# CCR4.net
KiCad netlist of a schematic drawn in EAGLE
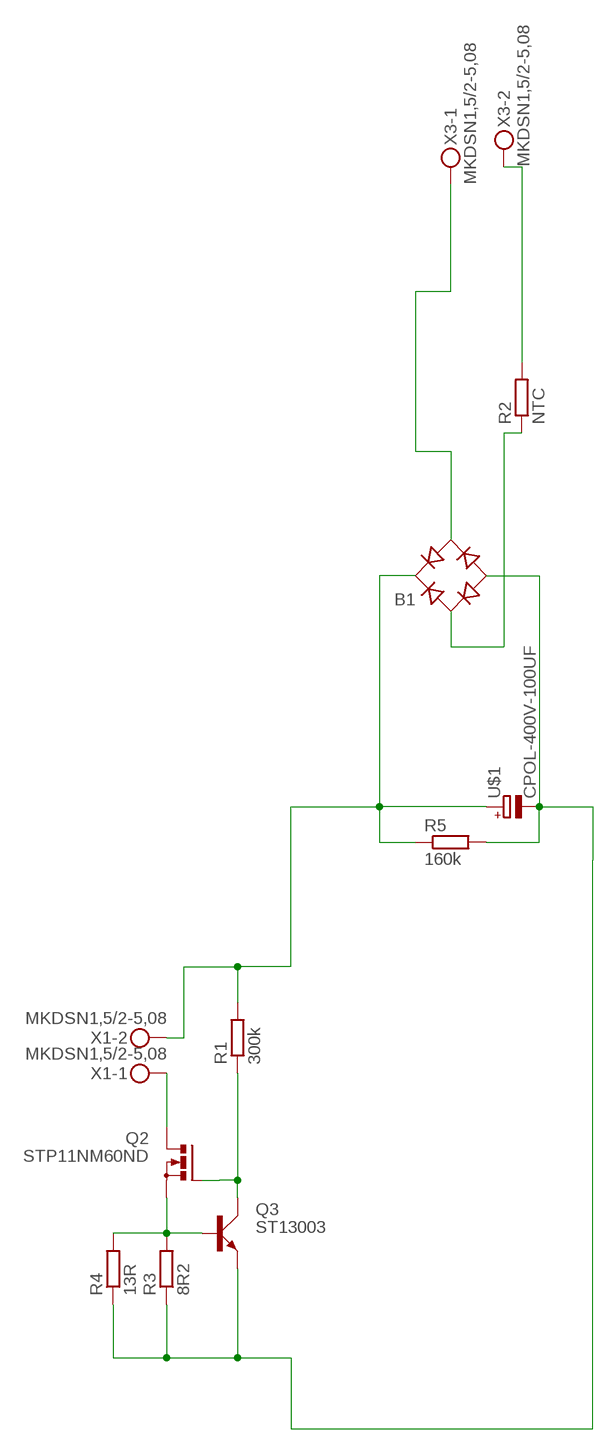
[diagram p0: schematic, sheet 1]

(export (version "E")
  (design (tool "Eeschema 10.0.6"))
  (components
    (comp (ref "B1")
      (value "RB1A")
      (footprint "eagle-import:RB1A")
      (libsource (lib "eagle-import") (part "RB1A"))
    )
    (comp (ref "Q2")
      (value "STP11NM60ND")
      (footprint "eagle-import:TO220BV")
      (libsource (lib "eagle-import") (part "BUZ11BV"))
    )
    (comp (ref "Q3")
      (value "ST13003")
      (footprint "eagle-import:SOT-92WIDE")
      (libsource (lib "eagle-import") (part "KSP42TA"))
    )
    (comp (ref "R1")
      (value "300k")
      (footprint "eagle-import:0411_12")
      (libsource (lib "eagle-import") (part "R-EU_0411/12"))
    )
    (comp (ref "R2")
      (value "NTC")
      (footprint "eagle-import:0309_10")
      (libsource (lib "eagle-import") (part "R-EU_0309/10"))
    )
    (comp (ref "R3")
      (value "8R2")
      (footprint "eagle-import:0411_12")
      (libsource (lib "eagle-import") (part "R-EU_0411/12"))
    )
    (comp (ref "R4")
      (value "13R")
      (footprint "eagle-import:0411_12")
      (libsource (lib "eagle-import") (part "R-EU_0411/12"))
    )
    (comp (ref "R5")
      (value "160k")
      (footprint "eagle-import:0204_7")
      (libsource (lib "eagle-import") (part "R-EU_0204/7"))
    )
    (comp (ref "U$1")
      (value "CPOL-400V-100UF")
      (footprint "eagle-import:18_36.5_7.62")
      (libsource (lib "eagle-import") (part "CPOL-400V-100UF"))
    )
    (comp (ref "X1")
      (value "MKDSN1,5/2-5,08")
      (footprint "eagle-import:MKDSN1,5_2-5,08")
      (libsource (lib "eagle-import") (part "MKDSN1,5/2-5,08"))
    )
    (comp (ref "X3")
      (value "MKDSN1,5/2-5,08")
      (footprint "eagle-import:MKDSN1,5_2-5,08")
      (libsource (lib "eagle-import") (part "MKDSN1,5/2-5,08"))
    )
  )
  (nets
    (net (code "1") (name "Net-(B1-PadAC1)") (class "Default")
      (node (ref "B1") (pin "AC1") (pinfunction "AC1_AC1") (pintype "passive"))
      (node (ref "R2") (pin "1") (pinfunction "1_1") (pintype "passive"))
    )
    (net (code "2") (name "Net-(Q2-PadG)") (class "Default")
      (node (ref "Q2") (pin "G") (pinfunction "G_G") (pintype "passive"))
      (node (ref "Q3") (pin "C") (pinfunction "C_C") (pintype "passive"))
      (node (ref "R1") (pin "1") (pinfunction "1_1") (pintype "passive"))
    )
    (net (code "3") (name "Net-(Q2-PadS)") (class "Default")
      (node (ref "Q2") (pin "S") (pinfunction "S_S") (pintype "passive"))
      (node (ref "Q3") (pin "B") (pinfunction "B_B") (pintype "passive"))
      (node (ref "R3") (pin "2") (pinfunction "2_2") (pintype "passive"))
      (node (ref "R4") (pin "2") (pinfunction "2_2") (pintype "passive"))
    )
    (net (code "4") (name "Net-(U$1-+)") (class "Default")
      (node (ref "B1") (pin "+") (pinfunction "+_+") (pintype "passive"))
      (node (ref "R1") (pin "2") (pinfunction "2_2") (pintype "passive"))
      (node (ref "R5") (pin "1") (pinfunction "1_1") (pintype "passive"))
      (node (ref "U$1") (pin "P$2") (pinfunction "+_P$2") (pintype "passive"))
      (node (ref "X1") (pin "2") (pinfunction "KL_2") (pintype "passive"))
    )
    (net (code "5") (name "Net-(U$1--)") (class "Default")
      (node (ref "B1") (pin "-") (pinfunction "-_-") (pintype "passive"))
      (node (ref "Q3") (pin "E") (pinfunction "E_E") (pintype "passive"))
      (node (ref "R3") (pin "1") (pinfunction "1_1") (pintype "passive"))
      (node (ref "R4") (pin "1") (pinfunction "1_1") (pintype "passive"))
      (node (ref "R5") (pin "2") (pinfunction "2_2") (pintype "passive"))
      (node (ref "U$1") (pin "P$1") (pinfunction "-_P$1") (pintype "passive"))
    )
    (net (code "6") (name "Net-(X1A-KL)") (class "Default")
      (node (ref "Q2") (pin "D") (pinfunction "D_D") (pintype "passive"))
      (node (ref "X1") (pin "1") (pinfunction "KL_1") (pintype "passive"))
    )
    (net (code "7") (name "Net-(X3A-KL)") (class "Default")
      (node (ref "B1") (pin "AC2") (pinfunction "AC2_AC2") (pintype "passive"))
      (node (ref "X3") (pin "1") (pinfunction "KL_1") (pintype "passive"))
    )
    (net (code "8") (name "Net-(X3B-KL)") (class "Default")
      (node (ref "R2") (pin "2") (pinfunction "2_2") (pintype "passive"))
      (node (ref "X3") (pin "2") (pinfunction "KL_2") (pintype "passive"))
    )
  )
)
